# ebook_reader.net
KiCad netlist of a schematic drawn in EAGLE
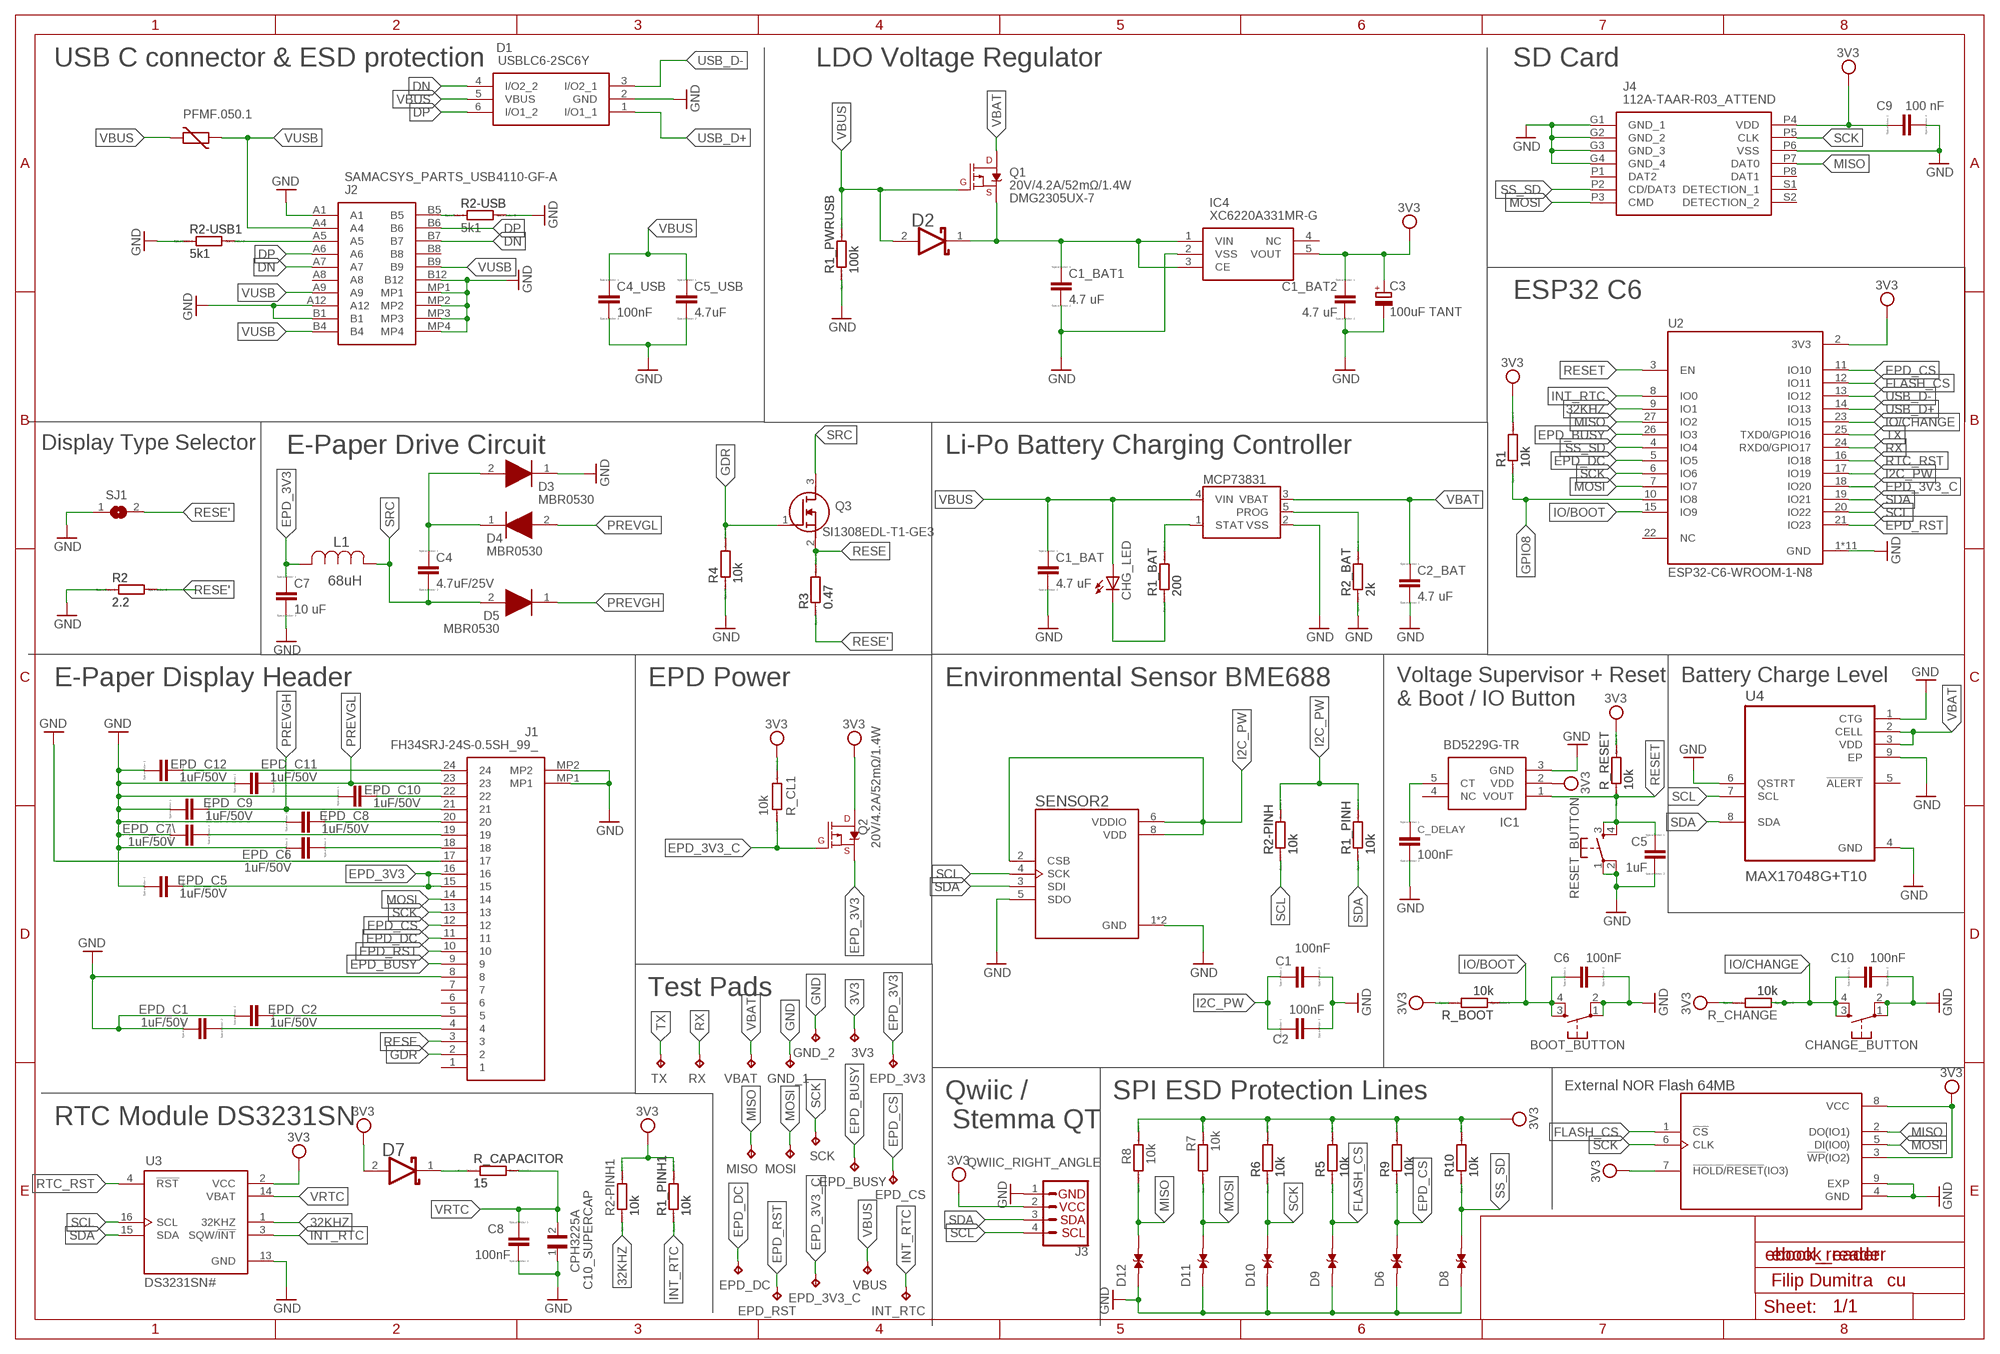
[diagram p0: schematic, sheet 1]

(export (version "E")
  (design (tool "Eeschema 10.0.6"))
  (components
    (comp (ref "3V3")
      (value "TPTP20R")
      (footprint "eagle-import:TP20R")
      (libsource (lib "eagle-import") (part "TPTP20R"))
    )
    (comp (ref "BOOT_BUTTON")
      (value "BUTTON_CUSYOMV1")
      (footprint "eagle-import:MYBUTTON")
      (libsource (lib "eagle-import") (part "BUTTON_CUSYOMV1"))
    )
    (comp (ref "C1")
      (value "100nF")
      (footprint "eagle-import:ESP32_WROVER_EAGLE-LTSPICE_C0402")
      (libsource (lib "eagle-import") (part "ESP32_WROVER_EAGLE-LTSPICE_CC0402"))
    )
    (comp (ref "C1_BAT")
      (value "4.7 uF")
      (footprint "eagle-import:ESP32_WROVER_EAGLE-LTSPICE_C0402")
      (libsource (lib "eagle-import") (part "ESP32_WROVER_EAGLE-LTSPICE_CC0402"))
    )
    (comp (ref "C1_BAT1")
      (value "4.7 uF")
      (footprint "eagle-import:ESP32_WROVER_EAGLE-LTSPICE_C0402")
      (libsource (lib "eagle-import") (part "ESP32_WROVER_EAGLE-LTSPICE_CC0402"))
    )
    (comp (ref "C1_BAT2")
      (value "4.7 uF")
      (footprint "eagle-import:ESP32_WROVER_EAGLE-LTSPICE_C0402")
      (libsource (lib "eagle-import") (part "ESP32_WROVER_EAGLE-LTSPICE_CC0402"))
    )
    (comp (ref "C2")
      (value "100nF")
      (footprint "eagle-import:ESP32_WROVER_EAGLE-LTSPICE_C0402")
      (libsource (lib "eagle-import") (part "ESP32_WROVER_EAGLE-LTSPICE_CC0402"))
    )
    (comp (ref "C2_BAT")
      (value "4.7 uF")
      (footprint "eagle-import:ESP32_WROVER_EAGLE-LTSPICE_C0402")
      (libsource (lib "eagle-import") (part "ESP32_WROVER_EAGLE-LTSPICE_CC0402"))
    )
    (comp (ref "C3")
      (value "100uF TANT")
      (footprint "eagle-import:RCL_CT3528")
      (libsource (lib "eagle-import") (part "RCL_CPOL-EUCT3528"))
    )
    (comp (ref "C4")
      (value "4.7uF/25V")
      (footprint "eagle-import:ESP32_WROVER_EAGLE-LTSPICE_C0402")
      (libsource (lib "eagle-import") (part "ESP32_WROVER_EAGLE-LTSPICE_CC0402"))
    )
    (comp (ref "C4_USB")
      (value "100nF")
      (footprint "eagle-import:ESP32_WROVER_EAGLE-LTSPICE_C0402")
      (libsource (lib "eagle-import") (part "ESP32_WROVER_EAGLE-LTSPICE_CC0402"))
    )
    (comp (ref "C5")
      (value "1uF")
      (footprint "eagle-import:ESP32_WROVER_EAGLE-LTSPICE_C0402")
      (libsource (lib "eagle-import") (part "ESP32_WROVER_EAGLE-LTSPICE_CC0402"))
    )
    (comp (ref "C5_USB")
      (value "4.7uF")
      (footprint "eagle-import:ESP32_WROVER_EAGLE-LTSPICE_C0402")
      (libsource (lib "eagle-import") (part "ESP32_WROVER_EAGLE-LTSPICE_CC0402"))
    )
    (comp (ref "C6")
      (value "100nF")
      (footprint "eagle-import:ESP32_WROVER_EAGLE-LTSPICE_C0402")
      (libsource (lib "eagle-import") (part "ESP32_WROVER_EAGLE-LTSPICE_CC0402"))
    )
    (comp (ref "C7")
      (value "10 uF")
      (footprint "eagle-import:ESP32_WROVER_EAGLE-LTSPICE_C0402")
      (libsource (lib "eagle-import") (part "ESP32_WROVER_EAGLE-LTSPICE_CC0402"))
    )
    (comp (ref "C8")
      (value "100nF")
      (footprint "eagle-import:ESP32_WROVER_EAGLE-LTSPICE_C0402")
      (libsource (lib "eagle-import") (part "ESP32_WROVER_EAGLE-LTSPICE_CC0402"))
    )
    (comp (ref "C9")
      (value "100 nF")
      (footprint "eagle-import:ESP32_WROVER_EAGLE-LTSPICE_C0402")
      (libsource (lib "eagle-import") (part "ESP32_WROVER_EAGLE-LTSPICE_CC0402"))
    )
    (comp (ref "C10")
      (value "100nF")
      (footprint "eagle-import:ESP32_WROVER_EAGLE-LTSPICE_C0402")
      (libsource (lib "eagle-import") (part "ESP32_WROVER_EAGLE-LTSPICE_CC0402"))
    )
    (comp (ref "C10_SUPERCAP")
      (value "CPH3225A")
      (footprint "eagle-import:CAPCP3225X100N")
      (fields (field (name "MF") "Seiko Instruments"))
      (libsource (lib "eagle-import") (part "CPH3225A"))
    )
    (comp (ref "CHANGE_BUTTON")
      (value "BUTTON_CUSYOMV1")
      (footprint "eagle-import:MYBUTTON")
      (libsource (lib "eagle-import") (part "BUTTON_CUSYOMV1"))
    )
    (comp (ref "CHG_LED")
      (value "ADAFRUIT_LEDCHIP-LED0603")
      (footprint "eagle-import:ADAFRUIT_CHIP-LED0603")
      (libsource (lib "eagle-import") (part "ADAFRUIT_LEDCHIP-LED0603"))
    )
    (comp (ref "C_DELAY")
      (value "100nF")
      (footprint "eagle-import:ESP32_WROVER_EAGLE-LTSPICE_C0402")
      (libsource (lib "eagle-import") (part "ESP32_WROVER_EAGLE-LTSPICE_CC0402"))
    )
    (comp (ref "D1")
      (value "USBLC6-2SC6Y")
      (footprint "eagle-import:SOT95P280X145-6N")
      (fields (field (name "MF") "STMicroelectronics"))
      (libsource (lib "eagle-import") (part "USBLC6-2SC6Y"))
    )
    (comp (ref "D2")
      (value "ESP32_WROVER_AVX---SD0805S020S1R0_AVX_SD0805S020S1R0_0_0AVX_SD0805S020S1R0_0_0")
      (footprint "eagle-import:ESP32_WROVER_AVX---SD0805S020S1R0_AVX_SD0805S020S1R0_0")
      (fields
        (field (name "DIGIKEY_PART_NUMBER") "478-7800-1-ND")
        (field (name "MF") "AVX")
        (field (name "MOUSER_PART_NUMBER") "581-SD0805S020S1R0")
      )
      (libsource (lib "eagle-import") (part "ESP32_WROVER_AVX---SD0805S020S1R0_AVX_SD0805S020S1R0_0_0AVX_SD0805S020S1R0_0_0"))
    )
    (comp (ref "D3")
      (value "MBR0530")
      (footprint "eagle-import:SOD3716X135N")
      (fields (field (name "MF") "ON Semiconductor"))
      (libsource (lib "eagle-import") (part "MBR0530"))
    )
    (comp (ref "D4")
      (value "MBR0530")
      (footprint "eagle-import:SOD3716X135N")
      (fields (field (name "MF") "ON Semiconductor"))
      (libsource (lib "eagle-import") (part "MBR0530"))
    )
    (comp (ref "D5")
      (value "MBR0530")
      (footprint "eagle-import:SOD3716X135N")
      (fields (field (name "MF") "ON Semiconductor"))
      (libsource (lib "eagle-import") (part "MBR0530"))
    )
    (comp (ref "D6")
      (value "PGB1010603MR")
      (footprint "eagle-import:DIOC1608X36N")
      (fields (field (name "MF") "Littelfuse Inc."))
      (libsource (lib "eagle-import") (part "PGB1010603MR"))
    )
    (comp (ref "D7")
      (value "ESP32_WROVER_AVX---SD0805S020S1R0_AVX_SD0805S020S1R0_0_0AVX_SD0805S020S1R0_0_0")
      (footprint "eagle-import:ESP32_WROVER_AVX---SD0805S020S1R0_AVX_SD0805S020S1R0_0")
      (fields
        (field (name "DIGIKEY_PART_NUMBER") "478-7800-1-ND")
        (field (name "MF") "AVX")
        (field (name "MOUSER_PART_NUMBER") "581-SD0805S020S1R0")
      )
      (libsource (lib "eagle-import") (part "ESP32_WROVER_AVX---SD0805S020S1R0_AVX_SD0805S020S1R0_0_0AVX_SD0805S020S1R0_0_0"))
    )
    (comp (ref "D8")
      (value "PGB1010603MR")
      (footprint "eagle-import:DIOC1608X36N")
      (fields (field (name "MF") "Littelfuse Inc."))
      (libsource (lib "eagle-import") (part "PGB1010603MR"))
    )
    (comp (ref "D9")
      (value "PGB1010603MR")
      (footprint "eagle-import:DIOC1608X36N")
      (fields (field (name "MF") "Littelfuse Inc."))
      (libsource (lib "eagle-import") (part "PGB1010603MR"))
    )
    (comp (ref "D10")
      (value "PGB1010603MR")
      (footprint "eagle-import:DIOC1608X36N")
      (fields (field (name "MF") "Littelfuse Inc."))
      (libsource (lib "eagle-import") (part "PGB1010603MR"))
    )
    (comp (ref "D11")
      (value "PGB1010603MR")
      (footprint "eagle-import:DIOC1608X36N")
      (fields (field (name "MF") "Littelfuse Inc."))
      (libsource (lib "eagle-import") (part "PGB1010603MR"))
    )
    (comp (ref "D12")
      (value "PGB1010603MR")
      (footprint "eagle-import:DIOC1608X36N")
      (fields (field (name "MF") "Littelfuse Inc."))
      (libsource (lib "eagle-import") (part "PGB1010603MR"))
    )
    (comp (ref "EPD_3V3")
      (value "TPTP20R")
      (footprint "eagle-import:TP20R")
      (libsource (lib "eagle-import") (part "TPTP20R"))
    )
    (comp (ref "EPD_3V3_C")
      (value "TPTP20R")
      (footprint "eagle-import:TP20R")
      (libsource (lib "eagle-import") (part "TPTP20R"))
    )
    (comp (ref "EPD_BUSY")
      (value "TPTP20R")
      (footprint "eagle-import:TP20R")
      (libsource (lib "eagle-import") (part "TPTP20R"))
    )
    (comp (ref "EPD_C1")
      (value "1uF/50V")
      (footprint "eagle-import:ESP32_WROVER_EAGLE-LTSPICE_C0402")
      (libsource (lib "eagle-import") (part "ESP32_WROVER_EAGLE-LTSPICE_CC0402"))
    )
    (comp (ref "EPD_C2")
      (value "1uF/50V")
      (footprint "eagle-import:ESP32_WROVER_EAGLE-LTSPICE_C0402")
      (libsource (lib "eagle-import") (part "ESP32_WROVER_EAGLE-LTSPICE_CC0402"))
    )
    (comp (ref "EPD_C5")
      (value "1uF/50V")
      (footprint "eagle-import:ESP32_WROVER_EAGLE-LTSPICE_C0402")
      (libsource (lib "eagle-import") (part "ESP32_WROVER_EAGLE-LTSPICE_CC0402"))
    )
    (comp (ref "EPD_C6")
      (value "1uF/50V")
      (footprint "eagle-import:ESP32_WROVER_EAGLE-LTSPICE_C0402")
      (libsource (lib "eagle-import") (part "ESP32_WROVER_EAGLE-LTSPICE_CC0402"))
    )
    (comp (ref "EPD_C7\\")
      (value "1uF/50V")
      (footprint "eagle-import:ESP32_WROVER_EAGLE-LTSPICE_C0402")
      (libsource (lib "eagle-import") (part "ESP32_WROVER_EAGLE-LTSPICE_CC0402"))
    )
    (comp (ref "EPD_C8")
      (value "1uF/50V")
      (footprint "eagle-import:ESP32_WROVER_EAGLE-LTSPICE_C0402")
      (libsource (lib "eagle-import") (part "ESP32_WROVER_EAGLE-LTSPICE_CC0402"))
    )
    (comp (ref "EPD_C9")
      (value "1uF/50V")
      (footprint "eagle-import:ESP32_WROVER_EAGLE-LTSPICE_C0402")
      (libsource (lib "eagle-import") (part "ESP32_WROVER_EAGLE-LTSPICE_CC0402"))
    )
    (comp (ref "EPD_C10")
      (value "1uF/50V")
      (footprint "eagle-import:ESP32_WROVER_EAGLE-LTSPICE_C0402")
      (libsource (lib "eagle-import") (part "ESP32_WROVER_EAGLE-LTSPICE_CC0402"))
    )
    (comp (ref "EPD_C11")
      (value "1uF/50V")
      (footprint "eagle-import:ESP32_WROVER_EAGLE-LTSPICE_C0402")
      (libsource (lib "eagle-import") (part "ESP32_WROVER_EAGLE-LTSPICE_CC0402"))
    )
    (comp (ref "EPD_C12")
      (value "1uF/50V")
      (footprint "eagle-import:ESP32_WROVER_EAGLE-LTSPICE_C0402")
      (libsource (lib "eagle-import") (part "ESP32_WROVER_EAGLE-LTSPICE_CC0402"))
    )
    (comp (ref "EPD_CS")
      (value "TPTP20R")
      (footprint "eagle-import:TP20R")
      (libsource (lib "eagle-import") (part "TPTP20R"))
    )
    (comp (ref "EPD_DC")
      (value "TPTP20R")
      (footprint "eagle-import:TP20R")
      (libsource (lib "eagle-import") (part "TPTP20R"))
    )
    (comp (ref "EPD_RST")
      (value "TPTP20R")
      (footprint "eagle-import:TP20R")
      (libsource (lib "eagle-import") (part "TPTP20R"))
    )
    (comp (ref "GND_1")
      (value "TPTP20R")
      (footprint "eagle-import:TP20R")
      (libsource (lib "eagle-import") (part "TPTP20R"))
    )
    (comp (ref "GND_2")
      (value "TPTP20R")
      (footprint "eagle-import:TP20R")
      (libsource (lib "eagle-import") (part "TPTP20R"))
    )
    (comp (ref "IC1")
      (value "BD5229G-TR")
      (footprint "eagle-import:SOT95P280X125-5N")
      (fields (field (name "MOUSER_PART_NUMBER") "755-BD5229G-TR"))
      (libsource (lib "eagle-import") (part "BD5229G-TR"))
    )
    (comp (ref "IC4")
      (value "XC6220A331MR-G")
      (footprint "eagle-import:SOT95P280X120-5N")
      (fields (field (name "MOUSER_PART_NUMBER") "865-XC6220A331MR-G"))
      (libsource (lib "eagle-import") (part "XC6220A331MR-G"))
    )
    (comp (ref "INT_RTC")
      (value "TPTP20R")
      (footprint "eagle-import:TP20R")
      (libsource (lib "eagle-import") (part "TPTP20R"))
    )
    (comp (ref "J1")
      (value "FH34SRJ-24S-0.5SH_99_")
      (footprint "eagle-import:FH34SRJ24S05SH99")
      (fields
        (field (name "MANUFACTURER_PART_NUMBER") "FH34SRJ-24S-0.5SH(99)")
        (field (name "MOUSER_PART_NUMBER") "798-FH34SRJ24S05SH99")
      )
      (libsource (lib "eagle-import") (part "FH34SRJ-24S-0.5SH_99_"))
    )
    (comp (ref "J2")
      (value "SAMACSYS_PARTS_USB4110-GF-A")
      (footprint "eagle-import:SAMACSYS_PARTS_USB4110GFA")
      (fields
        (field (name "MANUFACTURER_PART_NUMBER") "USB4110-GF-A")
        (field (name "MOUSER_PART_NUMBER") "640-USB4110-GF-A")
      )
      (libsource (lib "eagle-import") (part "SAMACSYS_PARTS_USB4110-GF-A"))
    )
    (comp (ref "J3")
      (value "QWIIC_RIGHT_ANGLE")
      (footprint "eagle-import:JST04_1MM_RA")
      (libsource (lib "eagle-import") (part "QWIIC_CONNECTORJS-1MM"))
    )
    (comp (ref "J4")
      (value "112A-TAAR-R03_ATTEND")
      (footprint "eagle-import:112ATAARR03ATTEND")
      (fields (field (name "MANUFACTURER_PART_NUMBER") "112A-TAAR-R03 ATTEND"))
      (libsource (lib "eagle-import") (part "112A-TAAR-R03_ATTEND"))
    )
    (comp (ref "L1")
      (value "68uH")
      (footprint "eagle-import:IND_4828-WE-TPC_WRE")
      (fields
        (field (name "MANUFACTURER_PART_NUMBER") "744043680")
        (field (name "COPYRIGHT") "Copyright (C) 2024 Ultra Librarian. All rights reserved.")
      )
      (libsource (lib "eagle-import") (part "744043680IND_4828-WE-TPC_WRE"))
    )
    (comp (ref "MCP73831")
      (value "ESP32_WROVER_SPARKFUN-IC-POWER_MCP73831")
      (footprint "eagle-import:ESP32_WROVER_SPARKFUN-IC-POWER_SOT23-5")
      (libsource (lib "eagle-import") (part "ESP32_WROVER_SPARKFUN-IC-POWER_MCP73831"))
    )
    (comp (ref "MISO")
      (value "TPTP20R")
      (footprint "eagle-import:TP20R")
      (libsource (lib "eagle-import") (part "TPTP20R"))
    )
    (comp (ref "MOSI")
      (value "TPTP20R")
      (footprint "eagle-import:TP20R")
      (libsource (lib "eagle-import") (part "TPTP20R"))
    )
    (comp (ref "PFMF.050.1")
      (value "ESP32C6_VARISTORCN1812")
      (footprint "eagle-import:ESP32C6_VARISTOR_CT_CN1812")
      (libsource (lib "eagle-import") (part "ESP32C6_VARISTORCN1812"))
    )
    (comp (ref "Q1")
      (value "20V/4.2A/52mΩ/1.4W")
      (footprint "eagle-import:ESP32_WROVER_SPARKFUN-DISCRETESEMI_SOT23-3")
      (libsource (lib "eagle-import") (part "ESP32_WROVER_SPARKFUN-DISCRETESEMI_MOSFET_PCH-DMG2305UX-7"))
    )
    (comp (ref "Q2")
      (value "20V/4.2A/52mΩ/1.4W")
      (footprint "eagle-import:ESP32_WROVER_SPARKFUN-DISCRETESEMI_SOT23-3")
      (libsource (lib "eagle-import") (part "ESP32_WROVER_SPARKFUN-DISCRETESEMI_MOSFET_PCH-DMG2305UX-7"))
    )
    (comp (ref "Q3")
      (value "SI1308EDL-T1-GE3")
      (footprint "eagle-import:SOT65P210X110-3N")
      (fields (field (name "MF") "Vishay Siliconix"))
      (libsource (lib "eagle-import") (part "SI1308EDL-T1-GE3"))
    )
    (comp (ref "R1")
      (value "10k")
      (footprint "eagle-import:ESP32_WROVER_EAGLE-LTSPICE_R0402")
      (libsource (lib "eagle-import") (part "ESP32_WROVER_EAGLE-LTSPICE_RR0402"))
    )
    (comp (ref "R1_BAT")
      (value "200")
      (footprint "eagle-import:ESP32_WROVER_EAGLE-LTSPICE_R0402")
      (libsource (lib "eagle-import") (part "ESP32_WROVER_EAGLE-LTSPICE_RR0402"))
    )
    (comp (ref "R1_PINH")
      (value "10k")
      (footprint "eagle-import:ESP32_WROVER_EAGLE-LTSPICE_R0402")
      (libsource (lib "eagle-import") (part "ESP32_WROVER_EAGLE-LTSPICE_RR0402"))
    )
    (comp (ref "R1_PINH1")
      (value "10k")
      (footprint "eagle-import:ESP32_WROVER_EAGLE-LTSPICE_R0402")
      (libsource (lib "eagle-import") (part "ESP32_WROVER_EAGLE-LTSPICE_RR0402"))
    )
    (comp (ref "R1_PWRUSB")
      (value "100k")
      (footprint "eagle-import:ESP32_WROVER_EAGLE-LTSPICE_R0402")
      (libsource (lib "eagle-import") (part "ESP32_WROVER_EAGLE-LTSPICE_RR0402"))
    )
    (comp (ref "R2")
      (value "2.2")
      (footprint "eagle-import:ESP32_WROVER_EAGLE-LTSPICE_R0402")
      (libsource (lib "eagle-import") (part "ESP32_WROVER_EAGLE-LTSPICE_RR0402"))
    )
    (comp (ref "R2-PINH")
      (value "10k")
      (footprint "eagle-import:ESP32_WROVER_EAGLE-LTSPICE_R0402")
      (libsource (lib "eagle-import") (part "ESP32_WROVER_EAGLE-LTSPICE_RR0402"))
    )
    (comp (ref "R2-PINH1")
      (value "10k")
      (footprint "eagle-import:ESP32_WROVER_EAGLE-LTSPICE_R0402")
      (libsource (lib "eagle-import") (part "ESP32_WROVER_EAGLE-LTSPICE_RR0402"))
    )
    (comp (ref "R2-USB")
      (value "5k1")
      (footprint "eagle-import:ESP32_WROVER_EAGLE-LTSPICE_R0402")
      (libsource (lib "eagle-import") (part "ESP32_WROVER_EAGLE-LTSPICE_RR0402"))
    )
    (comp (ref "R2-USB1")
      (value "5k1")
      (footprint "eagle-import:ESP32_WROVER_EAGLE-LTSPICE_R0402")
      (libsource (lib "eagle-import") (part "ESP32_WROVER_EAGLE-LTSPICE_RR0402"))
    )
    (comp (ref "R2_BAT")
      (value "2k")
      (footprint "eagle-import:ESP32_WROVER_EAGLE-LTSPICE_R0402")
      (libsource (lib "eagle-import") (part "ESP32_WROVER_EAGLE-LTSPICE_RR0402"))
    )
    (comp (ref "R3")
      (value "0.47")
      (footprint "eagle-import:ESP32_WROVER_EAGLE-LTSPICE_R0402")
      (libsource (lib "eagle-import") (part "ESP32_WROVER_EAGLE-LTSPICE_RR0402"))
    )
    (comp (ref "R4")
      (value "10k")
      (footprint "eagle-import:ESP32_WROVER_EAGLE-LTSPICE_R0402")
      (libsource (lib "eagle-import") (part "ESP32_WROVER_EAGLE-LTSPICE_RR0402"))
    )
    (comp (ref "R5")
      (value "10k")
      (footprint "eagle-import:ESP32_WROVER_EAGLE-LTSPICE_R0402")
      (libsource (lib "eagle-import") (part "ESP32_WROVER_EAGLE-LTSPICE_RR0402"))
    )
    (comp (ref "R6")
      (value "10k")
      (footprint "eagle-import:ESP32_WROVER_EAGLE-LTSPICE_R0402")
      (libsource (lib "eagle-import") (part "ESP32_WROVER_EAGLE-LTSPICE_RR0402"))
    )
    (comp (ref "R7")
      (value "10k")
      (footprint "eagle-import:ESP32_WROVER_EAGLE-LTSPICE_R0402")
      (libsource (lib "eagle-import") (part "ESP32_WROVER_EAGLE-LTSPICE_RR0402"))
    )
    (comp (ref "R8")
      (value "10k")
      (footprint "eagle-import:ESP32_WROVER_EAGLE-LTSPICE_R0402")
      (libsource (lib "eagle-import") (part "ESP32_WROVER_EAGLE-LTSPICE_RR0402"))
    )
    (comp (ref "R9")
      (value "10k")
      (footprint "eagle-import:ESP32_WROVER_EAGLE-LTSPICE_R0402")
      (libsource (lib "eagle-import") (part "ESP32_WROVER_EAGLE-LTSPICE_RR0402"))
    )
    (comp (ref "R10")
      (value "10k")
      (footprint "eagle-import:ESP32_WROVER_EAGLE-LTSPICE_R0402")
      (libsource (lib "eagle-import") (part "ESP32_WROVER_EAGLE-LTSPICE_RR0402"))
    )
    (comp (ref "RESET_BUTTON")
      (value "BUTTON_CUSYOMV1")
      (footprint "eagle-import:MYBUTTON")
      (libsource (lib "eagle-import") (part "BUTTON_CUSYOMV1"))
    )
    (comp (ref "RX")
      (value "TPTP20R")
      (footprint "eagle-import:TP20R")
      (libsource (lib "eagle-import") (part "TPTP20R"))
    )
    (comp (ref "R_BOOT")
      (value "10k")
      (footprint "eagle-import:ESP32_WROVER_EAGLE-LTSPICE_R0402")
      (libsource (lib "eagle-import") (part "ESP32_WROVER_EAGLE-LTSPICE_RR0402"))
    )
    (comp (ref "R_CAPACITOR")
      (value "15")
      (footprint "eagle-import:ESP32_WROVER_EAGLE-LTSPICE_R0402")
      (libsource (lib "eagle-import") (part "ESP32_WROVER_EAGLE-LTSPICE_RR0402"))
    )
    (comp (ref "R_CHANGE")
      (value "10k")
      (footprint "eagle-import:ESP32_WROVER_EAGLE-LTSPICE_R0402")
      (libsource (lib "eagle-import") (part "ESP32_WROVER_EAGLE-LTSPICE_RR0402"))
    )
    (comp (ref "R_CL1")
      (value "10k")
      (footprint "eagle-import:ESP32_WROVER_EAGLE-LTSPICE_R0402")
      (libsource (lib "eagle-import") (part "ESP32_WROVER_EAGLE-LTSPICE_RR0402"))
    )
    (comp (ref "R_RESET")
      (value "10k")
      (footprint "eagle-import:ESP32_WROVER_EAGLE-LTSPICE_R0402")
      (libsource (lib "eagle-import") (part "ESP32_WROVER_EAGLE-LTSPICE_RR0402"))
    )
    (comp (ref "SCK")
      (value "TPTP20R")
      (footprint "eagle-import:TP20R")
      (libsource (lib "eagle-import") (part "TPTP20R"))
    )
    (comp (ref "SENSOR2")
      (value "ESP32_WROVER_BME680_BME680")
      (footprint "eagle-import:ESP32_WROVER_BME680_PSON80P300X300X100-8N")
      (fields (field (name "MF") "Bosch Sensortec") (field (name "MP") "BME680"))
      (libsource (lib "eagle-import") (part "ESP32_WROVER_BME680_BME680"))
    )
    (comp (ref "SJ1") (value "SJ") (footprint "eagle-import:SJ") (libsource (lib "eagle-import") (part "SJ")))
    (comp (ref "TX")
      (value "TPTP20R")
      (footprint "eagle-import:TP20R")
      (libsource (lib "eagle-import") (part "TPTP20R"))
    )
    (comp (ref "U1")
      (value "W25Q512JVEIQ")
      (footprint "eagle-import:SON127P600X800X80-9N")
      (fields (field (name "MF") "Winbond Electronics"))
      (libsource (lib "eagle-import") (part "W25Q512JVEIQ"))
    )
    (comp (ref "U2")
      (value "ESP32-C6-WROOM-1-N8")
      (footprint "eagle-import:XCVR_ESP32-C6-WROOM-1-N8")
      (fields (field (name "MF") "Espressif Systems"))
      (libsource (lib "eagle-import") (part "ESP32-C6-WROOM-1-N8"))
    )
    (comp (ref "U3")
      (value "DS3231SN#")
      (footprint "eagle-import:SOIC127P1032X265-16N")
      (fields (field (name "MF") "Analog Devices"))
      (libsource (lib "eagle-import") (part "DS3231SN#"))
    )
    (comp (ref "U4")
      (value "MAX17048G+T10")
      (footprint "eagle-import:SON50P200X200X80-9N")
      (fields (field (name "MF") "Analog Devices"))
      (libsource (lib "eagle-import") (part "MAX17048G+T10"))
    )
    (comp (ref "VBAT")
      (value "TPTP20R")
      (footprint "eagle-import:TP20R")
      (libsource (lib "eagle-import") (part "TPTP20R"))
    )
    (comp (ref "VBUS")
      (value "TPTP20R")
      (footprint "eagle-import:TP20R")
      (libsource (lib "eagle-import") (part "TPTP20R"))
    )
  )
  (nets
    (net (code "1") (name "3V3") (class "Default")
      (node (ref "3V3") (pin "TP") (pinfunction "TP_TP") (pintype "input"))
      (node (ref "C1_BAT2") (pin "1") (pinfunction "1_1") (pintype "passive"))
      (node (ref "C3") (pin "+") (pinfunction "+_+") (pintype "passive"))
      (node (ref "C9") (pin "1") (pinfunction "1_1") (pintype "passive"))
      (node (ref "D7") (pin "2") (pinfunction "ANODE_2") (pintype "bidirectional"))
      (node (ref "IC1") (pin "2") (pinfunction "VDD_2") (pintype "bidirectional"))
      (node (ref "IC4") (pin "5") (pinfunction "VOUT_5") (pintype "bidirectional"))
      (node (ref "J3") (pin "2") (pinfunction "2_2") (pintype "power_in"))
      (node (ref "J4") (pin "P4") (pinfunction "VDD_P4") (pintype "bidirectional"))
      (node (ref "Q2") (pin "3") (pinfunction "D_3") (pintype "bidirectional"))
      (node (ref "R1") (pin "2") (pinfunction "2_2") (pintype "passive"))
      (node (ref "R10") (pin "2") (pinfunction "2_2") (pintype "passive"))
      (node (ref "R1_PINH1") (pin "2") (pinfunction "2_2") (pintype "passive"))
      (node (ref "R2-PINH1") (pin "2") (pinfunction "2_2") (pintype "passive"))
      (node (ref "R5") (pin "2") (pinfunction "2_2") (pintype "passive"))
      (node (ref "R6") (pin "2") (pinfunction "2_2") (pintype "passive"))
      (node (ref "R7") (pin "2") (pinfunction "2_2") (pintype "passive"))
      (node (ref "R8") (pin "2") (pinfunction "2_2") (pintype "passive"))
      (node (ref "R9") (pin "2") (pinfunction "2_2") (pintype "passive"))
      (node (ref "R_BOOT") (pin "2") (pinfunction "2_2") (pintype "passive"))
      (node (ref "R_CHANGE") (pin "2") (pinfunction "2_2") (pintype "passive"))
      (node (ref "R_CL1") (pin "2") (pinfunction "2_2") (pintype "passive"))
      (node (ref "R_RESET") (pin "2") (pinfunction "2_2") (pintype "passive"))
      (node (ref "U1") (pin "3") (pinfunction "~{WP}(IO2)_3") (pintype "bidirectional"))
      (node (ref "U1") (pin "7") (pinfunction "~{HOLD}/~{RESET}(IO3)_7") (pintype "bidirectional"))
      (node (ref "U1") (pin "8") (pinfunction "VCC_8") (pintype "power_in"))
      (node (ref "U2") (pin "2") (pinfunction "3V3_2") (pintype "power_in"))
      (node (ref "U3") (pin "2") (pinfunction "VCC_2") (pintype "power_in"))
    )
    (net (code "2") (name "32KHZ") (class "Default")
      (node (ref "R2-PINH1") (pin "1") (pinfunction "1_1") (pintype "passive"))
      (node (ref "U2") (pin "9") (pinfunction "IO1_9") (pintype "bidirectional"))
      (node (ref "U3") (pin "1") (pinfunction "32KHZ_1") (pintype "output"))
    )
    (net (code "3") (name "DN") (class "Default")
      (node (ref "D1") (pin "4") (pinfunction "I/O2_2_4") (pintype "bidirectional"))
      (node (ref "J2") (pin "A7") (pinfunction "A7_A7") (pintype "bidirectional"))
      (node (ref "J2") (pin "B7") (pinfunction "B7_B7") (pintype "bidirectional"))
    )
    (net (code "4") (name "DP") (class "Default")
      (node (ref "D1") (pin "6") (pinfunction "I/O1_2_6") (pintype "bidirectional"))
      (node (ref "J2") (pin "A6") (pinfunction "A6_A6") (pintype "bidirectional"))
      (node (ref "J2") (pin "B6") (pinfunction "B6_B6") (pintype "bidirectional"))
    )
    (net (code "5") (name "EPD_3V3") (class "Default")
      (node (ref "C7") (pin "1") (pinfunction "1_1") (pintype "passive"))
      (node (ref "EPD_3V3") (pin "TP") (pinfunction "TP_TP") (pintype "input"))
      (node (ref "EPD_C5") (pin "2") (pinfunction "2_2") (pintype "passive"))
      (node (ref "J1") (pin "15") (pinfunction "15_15") (pintype "bidirectional"))
      (node (ref "J1") (pin "16") (pinfunction "16_16") (pintype "bidirectional"))
      (node (ref "L1") (pin "2") (pinfunction "2_2") (pintype "passive"))
      (node (ref "Q2") (pin "2") (pinfunction "S_2") (pintype "bidirectional"))
    )
    (net (code "6") (name "EPD_3V3_C") (class "Default")
      (node (ref "EPD_3V3_C") (pin "TP") (pinfunction "TP_TP") (pintype "input"))
      (node (ref "Q2") (pin "1") (pinfunction "G_1") (pintype "bidirectional"))
      (node (ref "R_CL1") (pin "1") (pinfunction "1_1") (pintype "passive"))
      (node (ref "U2") (pin "18") (pinfunction "IO20_18") (pintype "bidirectional"))
    )
    (net (code "7") (name "EPD_BUSY") (class "Default")
      (node (ref "EPD_BUSY") (pin "TP") (pinfunction "TP_TP") (pintype "input"))
      (node (ref "J1") (pin "9") (pinfunction "9_9") (pintype "bidirectional"))
      (node (ref "U2") (pin "26") (pinfunction "IO3_26") (pintype "bidirectional"))
    )
    (net (code "8") (name "EPD_CS") (class "Default")
      (node (ref "D6") (pin "2") (pinfunction "2_2") (pintype "passive"))
      (node (ref "EPD_CS") (pin "TP") (pinfunction "TP_TP") (pintype "input"))
      (node (ref "J1") (pin "12") (pinfunction "12_12") (pintype "bidirectional"))
      (node (ref "R9") (pin "1") (pinfunction "1_1") (pintype "passive"))
      (node (ref "U2") (pin "11") (pinfunction "IO10_11") (pintype "bidirectional"))
    )
    (net (code "9") (name "EPD_DC") (class "Default")
      (node (ref "EPD_DC") (pin "TP") (pinfunction "TP_TP") (pintype "input"))
      (node (ref "J1") (pin "11") (pinfunction "11_11") (pintype "bidirectional"))
      (node (ref "U2") (pin "5") (pinfunction "IO5_5") (pintype "bidirectional"))
    )
    (net (code "10") (name "EPD_RST") (class "Default")
      (node (ref "EPD_RST") (pin "TP") (pinfunction "TP_TP") (pintype "input"))
      (node (ref "J1") (pin "10") (pinfunction "10_10") (pintype "bidirectional"))
      (node (ref "U2") (pin "21") (pinfunction "IO23_21") (pintype "bidirectional"))
    )
    (net (code "11") (name "FLASH_CS") (class "Default")
      (node (ref "D9") (pin "2") (pinfunction "2_2") (pintype "passive"))
      (node (ref "R5") (pin "1") (pinfunction "1_1") (pintype "passive"))
      (node (ref "U1") (pin "1") (pinfunction "~{CS}_1") (pintype "input"))
      (node (ref "U2") (pin "12") (pinfunction "IO11_12") (pintype "bidirectional"))
    )
    (net (code "12") (name "GDR") (class "Default")
      (node (ref "J1") (pin "2") (pinfunction "2_2") (pintype "bidirectional"))
      (node (ref "Q3") (pin "1") (pinfunction "G_1") (pintype "bidirectional"))
      (node (ref "R4") (pin "2") (pinfunction "2_2") (pintype "passive"))
    )
    (net (code "13") (name "GND") (class "Default")
      (node (ref "BOOT_BUTTON") (pin "1") (pinfunction "1_1") (pintype "passive"))
      (node (ref "BOOT_BUTTON") (pin "2") (pinfunction "2_2") (pintype "passive"))
      (node (ref "C1") (pin "2") (pinfunction "2_2") (pintype "passive"))
      (node (ref "C10") (pin "2") (pinfunction "2_2") (pintype "passive"))
      (node (ref "C10_SUPERCAP") (pin "1") (pinfunction "1_1") (pintype "passive"))
      (node (ref "C1_BAT") (pin "2") (pinfunction "2_2") (pintype "passive"))
      (node (ref "C1_BAT1") (pin "2") (pinfunction "2_2") (pintype "passive"))
      (node (ref "C1_BAT2") (pin "2") (pinfunction "2_2") (pintype "passive"))
      (node (ref "C2") (pin "2") (pinfunction "2_2") (pintype "passive"))
      (node (ref "C2_BAT") (pin "2") (pinfunction "2_2") (pintype "passive"))
      (node (ref "C3") (pin "-") (pinfunction "-_-") (pintype "passive"))
      (node (ref "C4_USB") (pin "2") (pinfunction "2_2") (pintype "passive"))
      (node (ref "C5") (pin "2") (pinfunction "2_2") (pintype "passive"))
      (node (ref "C5_USB") (pin "2") (pinfunction "2_2") (pintype "passive"))
      (node (ref "C6") (pin "2") (pinfunction "2_2") (pintype "passive"))
      (node (ref "C7") (pin "2") (pinfunction "2_2") (pintype "passive"))
      (node (ref "C8") (pin "2") (pinfunction "2_2") (pintype "passive"))
      (node (ref "C9") (pin "2") (pinfunction "2_2") (pintype "passive"))
      (node (ref "CHANGE_BUTTON") (pin "1") (pinfunction "1_1") (pintype "passive"))
      (node (ref "CHANGE_BUTTON") (pin "2") (pinfunction "2_2") (pintype "passive"))
      (node (ref "C_DELAY") (pin "2") (pinfunction "2_2") (pintype "passive"))
      (node (ref "D1") (pin "2") (pinfunction "GND_2") (pintype "bidirectional"))
      (node (ref "D10") (pin "1") (pinfunction "1_1") (pintype "passive"))
      (node (ref "D11") (pin "1") (pinfunction "1_1") (pintype "passive"))
      (node (ref "D12") (pin "1") (pinfunction "1_1") (pintype "passive"))
      (node (ref "D3") (pin "1") (pinfunction "K_1") (pintype "bidirectional"))
      (node (ref "D6") (pin "1") (pinfunction "1_1") (pintype "passive"))
      (node (ref "D8") (pin "1") (pinfunction "1_1") (pintype "passive"))
      (node (ref "D9") (pin "1") (pinfunction "1_1") (pintype "passive"))
      (node (ref "EPD_C1") (pin "1") (pinfunction "1_1") (pintype "passive"))
      (node (ref "EPD_C10") (pin "1") (pinfunction "1_1") (pintype "passive"))
      (node (ref "EPD_C11") (pin "1") (pinfunction "1_1") (pintype "passive"))
      (node (ref "EPD_C12") (pin "1") (pinfunction "1_1") (pintype "passive"))
      (node (ref "EPD_C2") (pin "1") (pinfunction "1_1") (pintype "passive"))
      (node (ref "EPD_C5") (pin "1") (pinfunction "1_1") (pintype "passive"))
      (node (ref "EPD_C6") (pin "1") (pinfunction "1_1") (pintype "passive"))
      (node (ref "EPD_C7\\") (pin "1") (pinfunction "1_1") (pintype "passive"))
      (node (ref "EPD_C8") (pin "1") (pinfunction "1_1") (pintype "passive"))
      (node (ref "EPD_C9") (pin "1") (pinfunction "1_1") (pintype "passive"))
      (node (ref "GND_1") (pin "TP") (pinfunction "TP_TP") (pintype "input"))
      (node (ref "GND_2") (pin "TP") (pinfunction "TP_TP") (pintype "input"))
      (node (ref "IC1") (pin "3") (pinfunction "GND_3") (pintype "bidirectional"))
      (node (ref "IC4") (pin "2") (pinfunction "VSS_2") (pintype "bidirectional"))
      (node (ref "J1") (pin "17") (pinfunction "17_17") (pintype "bidirectional"))
      (node (ref "J1") (pin "8") (pinfunction "8_8") (pintype "bidirectional"))
      (node (ref "J1") (pin "MP1") (pinfunction "MP1_MP1") (pintype "bidirectional"))
      (node (ref "J1") (pin "MP2") (pinfunction "MP2_MP2") (pintype "bidirectional"))
      (node (ref "J2") (pin "A1") (pinfunction "A1_A1") (pintype "bidirectional"))
      (node (ref "J2") (pin "A12") (pinfunction "A12_A12") (pintype "bidirectional"))
      (node (ref "J2") (pin "B1") (pinfunction "B1_B1") (pintype "bidirectional"))
      (node (ref "J2") (pin "B12") (pinfunction "B12_B12") (pintype "bidirectional"))
      (node (ref "J2") (pin "MP1") (pinfunction "MP1_MP1") (pintype "bidirectional"))
      (node (ref "J2") (pin "MP2") (pinfunction "MP2_MP2") (pintype "bidirectional"))
      (node (ref "J2") (pin "MP3") (pinfunction "MP3_MP3") (pintype "bidirectional"))
      (node (ref "J2") (pin "MP4") (pinfunction "MP4_MP4") (pintype "bidirectional"))
      (node (ref "J3") (pin "1") (pinfunction "1_1") (pintype "power_in"))
      (node (ref "J4") (pin "G1") (pinfunction "GND_1_G1") (pintype "bidirectional"))
      (node (ref "J4") (pin "G2") (pinfunction "GND_2_G2") (pintype "bidirectional"))
      (node (ref "J4") (pin "G3") (pinfunction "GND_3_G3") (pintype "bidirectional"))
      (node (ref "J4") (pin "G4") (pinfunction "GND_4_G4") (pintype "bidirectional"))
      (node (ref "J4") (pin "P6") (pinfunction "VSS_P6") (pintype "bidirectional"))
      (node (ref "MCP73831") (pin "2") (pinfunction "VSS_2") (pintype "power_in"))
      (node (ref "R1_PWRUSB") (pin "1") (pinfunction "1_1") (pintype "passive"))
      (node (ref "R2") (pin "1") (pinfunction "1_1") (pintype "passive"))
      (node (ref "R2-USB") (pin "2") (pinfunction "2_2") (pintype "passive"))
      (node (ref "R2-USB1") (pin "1") (pinfunction "1_1") (pintype "passive"))
      (node (ref "R2_BAT") (pin "1") (pinfunction "1_1") (pintype "passive"))
      (node (ref "R4") (pin "1") (pinfunction "1_1") (pintype "passive"))
      (node (ref "RESET_BUTTON") (pin "1") (pinfunction "1_1") (pintype "passive"))
      (node (ref "RESET_BUTTON") (pin "2") (pinfunction "2_2") (pintype "passive"))
      (node (ref "SENSOR2") (pin "1") (pinfunction "GND_1") (pintype "power_in"))
      (node (ref "SENSOR2") (pin "5") (pinfunction "SDO_5") (pintype "bidirectional"))
      (node (ref "SENSOR2") (pin "7") (pinfunction "GND_7") (pintype "power_in"))
      (node (ref "SJ1") (pin "1") (pinfunction "1_1") (pintype "passive"))
      (node (ref "U1") (pin "4") (pinfunction "GND_4") (pintype "power_in"))
      (node (ref "U1") (pin "9") (pinfunction "EXP_9") (pintype "passive"))
      (node (ref "U2") (pin "1") (pinfunction "GND_1") (pintype "power_in"))
      (node (ref "U2") (pin "28") (pinfunction "GND_28") (pintype "power_in"))
      (node (ref "U2") (pin "29_1") (pinfunction "GND_29_1") (pintype "power_in"))
      (node (ref "U2") (pin "29_2") (pinfunction "GND_29_2") (pintype "power_in"))
      (node (ref "U2") (pin "29_3") (pinfunction "GND_29_3") (pintype "power_in"))
      (node (ref "U2") (pin "29_4") (pinfunction "GND_29_4") (pintype "power_in"))
      (node (ref "U2") (pin "29_5") (pinfunction "GND_29_5") (pintype "power_in"))
      (node (ref "U2") (pin "29_6") (pinfunction "GND_29_6") (pintype "power_in"))
      (node (ref "U2") (pin "29_7") (pinfunction "GND_29_7") (pintype "power_in"))
      (node (ref "U2") (pin "29_8") (pinfunction "GND_29_8") (pintype "power_in"))
      (node (ref "U2") (pin "29_9") (pinfunction "GND_29_9") (pintype "power_in"))
      (node (ref "U3") (pin "13") (pinfunction "GND_13") (pintype "power_in"))
      (node (ref "U4") (pin "1") (pinfunction "CTG_1") (pintype "power_in"))
      (node (ref "U4") (pin "4") (pinfunction "GND_4") (pintype "power_in"))
      (node (ref "U4") (pin "6") (pinfunction "QSTRT_6") (pintype "input"))
      (node (ref "U4") (pin "9") (pinfunction "EP_9") (pintype "power_in"))
    )
    (net (code "14") (name "GPIO8") (class "Default")
      (node (ref "R1") (pin "1") (pinfunction "1_1") (pintype "passive"))
      (node (ref "U2") (pin "10") (pinfunction "IO8_10") (pintype "bidirectional"))
    )
    (net (code "15") (name "I2C_PW") (class "Default")
      (node (ref "C1") (pin "1") (pinfunction "1_1") (pintype "passive"))
      (node (ref "C2") (pin "1") (pinfunction "1_1") (pintype "passive"))
      (node (ref "R1_PINH") (pin "2") (pinfunction "2_2") (pintype "passive"))
      (node (ref "R2-PINH") (pin "2") (pinfunction "2_2") (pintype "passive"))
      (node (ref "SENSOR2") (pin "2") (pinfunction "CSB_2") (pintype "input"))
      (node (ref "SENSOR2") (pin "6") (pinfunction "VDDIO_6") (pintype "power_in"))
      (node (ref "SENSOR2") (pin "8") (pinfunction "VDD_8") (pintype "power_in"))
      (node (ref "U2") (pin "17") (pinfunction "IO19_17") (pintype "bidirectional"))
    )
    (net (code "16") (name "INT_RTC") (class "Default")
      (node (ref "INT_RTC") (pin "TP") (pinfunction "TP_TP") (pintype "input"))
      (node (ref "R1_PINH1") (pin "1") (pinfunction "1_1") (pintype "passive"))
      (node (ref "U2") (pin "8") (pinfunction "IO0_8") (pintype "bidirectional"))
      (node (ref "U3") (pin "3") (pinfunction "SQW/~{INT}_3") (pintype "output"))
    )
    (net (code "17") (name "IO{slash}BOOT") (class "Default")
      (node (ref "BOOT_BUTTON") (pin "3") (pinfunction "3_3") (pintype "passive"))
      (node (ref "BOOT_BUTTON") (pin "4") (pinfunction "4_4") (pintype "passive"))
      (node (ref "C6") (pin "1") (pinfunction "1_1") (pintype "passive"))
      (node (ref "R_BOOT") (pin "1") (pinfunction "1_1") (pintype "passive"))
      (node (ref "U2") (pin "15") (pinfunction "IO9_15") (pintype "bidirectional"))
    )
    (net (code "18") (name "IO{slash}CHANGE") (class "Default")
      (node (ref "C10") (pin "1") (pinfunction "1_1") (pintype "passive"))
      (node (ref "CHANGE_BUTTON") (pin "3") (pinfunction "3_3") (pintype "passive"))
      (node (ref "CHANGE_BUTTON") (pin "4") (pinfunction "4_4") (pintype "passive"))
      (node (ref "R_CHANGE") (pin "1") (pinfunction "1_1") (pintype "passive"))
      (node (ref "U2") (pin "23") (pinfunction "IO15_23") (pintype "bidirectional"))
    )
    (net (code "19") (name "MISO") (class "Default")
      (node (ref "D12") (pin "2") (pinfunction "2_2") (pintype "passive"))
      (node (ref "J4") (pin "P7") (pinfunction "DAT0_P7") (pintype "bidirectional"))
      (node (ref "MISO") (pin "TP") (pinfunction "TP_TP") (pintype "input"))
      (node (ref "R8") (pin "1") (pinfunction "1_1") (pintype "passive"))
      (node (ref "U1") (pin "2") (pinfunction "DO(IO1)_2") (pintype "bidirectional"))
      (node (ref "U2") (pin "27") (pinfunction "IO2_27") (pintype "bidirectional"))
    )
    (net (code "20") (name "MOSI") (class "Default")
      (node (ref "D11") (pin "2") (pinfunction "2_2") (pintype "passive"))
      (node (ref "J1") (pin "14") (pinfunction "14_14") (pintype "bidirectional"))
      (node (ref "J4") (pin "P3") (pinfunction "CMD_P3") (pintype "bidirectional"))
      (node (ref "MOSI") (pin "TP") (pinfunction "TP_TP") (pintype "input"))
      (node (ref "R7") (pin "1") (pinfunction "1_1") (pintype "passive"))
      (node (ref "U1") (pin "5") (pinfunction "DI(IO0)_5") (pintype "bidirectional"))
      (node (ref "U2") (pin "7") (pinfunction "IO7_7") (pintype "bidirectional"))
    )
    (net (code "21") (name "Net-(CHG_LED-PadC)") (class "Default")
      (node (ref "CHG_LED") (pin "C") (pinfunction "C_C") (pintype "passive"))
      (node (ref "R1_BAT") (pin "1") (pinfunction "1_1") (pintype "passive"))
    )
    (net (code "22") (name "Net-(D2-CATHODE)") (class "Default")
      (node (ref "C1_BAT1") (pin "1") (pinfunction "1_1") (pintype "passive"))
      (node (ref "D2") (pin "1") (pinfunction "CATHODE_1") (pintype "bidirectional"))
      (node (ref "IC4") (pin "1") (pinfunction "VIN_1") (pintype "bidirectional"))
      (node (ref "IC4") (pin "3") (pinfunction "CE_3") (pintype "bidirectional"))
      (node (ref "Q1") (pin "2") (pinfunction "S_2") (pintype "bidirectional"))
    )
    (net (code "23") (name "Net-(D3-A)") (class "Default")
      (node (ref "C4") (pin "1") (pinfunction "1_1") (pintype "passive"))
      (node (ref "D3") (pin "2") (pinfunction "A_2") (pintype "bidirectional"))
      (node (ref "D4") (pin "1") (pinfunction "K_1") (pintype "bidirectional"))
    )
    (net (code "24") (name "Net-(D7-CATHODE)") (class "Default")
      (node (ref "D7") (pin "1") (pinfunction "CATHODE_1") (pintype "bidirectional"))
      (node (ref "R_CAPACITOR") (pin "1") (pinfunction "1_1") (pintype "passive"))
    )
    (net (code "25") (name "Net-(EPD_C1-Pad2)") (class "Default")
      (node (ref "EPD_C1") (pin "2") (pinfunction "2_2") (pintype "passive"))
      (node (ref "J1") (pin "4") (pinfunction "4_4") (pintype "bidirectional"))
    )
    (net (code "26") (name "Net-(EPD_C2-Pad2)") (class "Default")
      (node (ref "EPD_C2") (pin "2") (pinfunction "2_2") (pintype "passive"))
      (node (ref "J1") (pin "5") (pinfunction "5_5") (pintype "bidirectional"))
    )
    (net (code "27") (name "Net-(EPD_C6-Pad2)") (class "Default")
      (node (ref "EPD_C6") (pin "2") (pinfunction "2_2") (pintype "passive"))
      (node (ref "J1") (pin "18") (pinfunction "18_18") (pintype "bidirectional"))
    )
    (net (code "28") (name "Net-(EPD_C7\\-Pad2)") (class "Default")
      (node (ref "EPD_C7\\") (pin "2") (pinfunction "2_2") (pintype "passive"))
      (node (ref "J1") (pin "19") (pinfunction "19_19") (pintype "bidirectional"))
    )
    (net (code "29") (name "Net-(EPD_C8-Pad2)") (class "Default")
      (node (ref "EPD_C8") (pin "2") (pinfunction "2_2") (pintype "passive"))
      (node (ref "J1") (pin "20") (pinfunction "20_20") (pintype "bidirectional"))
    )
    (net (code "30") (name "Net-(EPD_C10-Pad2)") (class "Default")
      (node (ref "EPD_C10") (pin "2") (pinfunction "2_2") (pintype "passive"))
      (node (ref "J1") (pin "22") (pinfunction "22_22") (pintype "bidirectional"))
    )
    (net (code "31") (name "Net-(EPD_C12-Pad2)") (class "Default")
      (node (ref "EPD_C12") (pin "2") (pinfunction "2_2") (pintype "passive"))
      (node (ref "J1") (pin "24") (pinfunction "24_24") (pintype "bidirectional"))
    )
    (net (code "32") (name "Net-(IC1-CT)") (class "Default")
      (node (ref "C_DELAY") (pin "1") (pinfunction "1_1") (pintype "passive"))
      (node (ref "IC1") (pin "5") (pinfunction "CT_5") (pintype "bidirectional"))
    )
    (net (code "33") (name "Net-(J2-PadA5)") (class "Default")
      (node (ref "J2") (pin "A5") (pinfunction "A5_A5") (pintype "bidirectional"))
      (node (ref "R2-USB1") (pin "2") (pinfunction "2_2") (pintype "passive"))
    )
    (net (code "34") (name "Net-(J2-PadB5)") (class "Default")
      (node (ref "J2") (pin "B5") (pinfunction "B5_B5") (pintype "bidirectional"))
      (node (ref "R2-USB") (pin "1") (pinfunction "1_1") (pintype "passive"))
    )
    (net (code "35") (name "Net-(MCP73831-PROG)") (class "Default")
      (node (ref "MCP73831") (pin "5") (pinfunction "PROG_5") (pintype "input"))
      (node (ref "R2_BAT") (pin "2") (pinfunction "2_2") (pintype "passive"))
    )
    (net (code "36") (name "Net-(MCP73831-STAT)") (class "Default")
      (node (ref "MCP73831") (pin "1") (pinfunction "STAT_1") (pintype "output"))
      (node (ref "R1_BAT") (pin "2") (pinfunction "2_2") (pintype "passive"))
    )
    (net (code "37") (name "PREVGH") (class "Default")
      (node (ref "D5") (pin "1") (pinfunction "K_1") (pintype "bidirectional"))
      (node (ref "EPD_C9") (pin "2") (pinfunction "2_2") (pintype "passive"))
      (node (ref "J1") (pin "21") (pinfunction "21_21") (pintype "bidirectional"))
    )
    (net (code "38") (name "PREVGL") (class "Default")
      (node (ref "D4") (pin "2") (pinfunction "A_2") (pintype "bidirectional"))
      (node (ref "EPD_C11") (pin "2") (pinfunction "2_2") (pintype "passive"))
      (node (ref "J1") (pin "23") (pinfunction "23_23") (pintype "bidirectional"))
    )
    (net (code "39") (name "RESE") (class "Default")
      (node (ref "J1") (pin "3") (pinfunction "3_3") (pintype "bidirectional"))
      (node (ref "Q3") (pin "2") (pinfunction "S_2") (pintype "bidirectional"))
      (node (ref "R3") (pin "2") (pinfunction "2_2") (pintype "passive"))
    )
    (net (code "40") (name "RESE'") (class "Default")
      (node (ref "R2") (pin "2") (pinfunction "2_2") (pintype "passive"))
      (node (ref "R3") (pin "1") (pinfunction "1_1") (pintype "passive"))
      (node (ref "SJ1") (pin "2") (pinfunction "2_2") (pintype "passive"))
    )
    (net (code "41") (name "RESET") (class "Default")
      (node (ref "C5") (pin "1") (pinfunction "1_1") (pintype "passive"))
      (node (ref "IC1") (pin "1") (pinfunction "VOUT_1") (pintype "bidirectional"))
      (node (ref "RESET_BUTTON") (pin "3") (pinfunction "3_3") (pintype "passive"))
      (node (ref "RESET_BUTTON") (pin "4") (pinfunction "4_4") (pintype "passive"))
      (node (ref "R_RESET") (pin "1") (pinfunction "1_1") (pintype "passive"))
      (node (ref "U2") (pin "3") (pinfunction "EN_3") (pintype "input"))
    )
    (net (code "42") (name "RTC_RST") (class "Default")
      (node (ref "U2") (pin "16") (pinfunction "IO18_16") (pintype "bidirectional"))
      (node (ref "U3") (pin "4") (pinfunction "~{RST}_4") (pintype "input"))
    )
    (net (code "43") (name "RX") (class "Default")
      (node (ref "RX") (pin "TP") (pinfunction "TP_TP") (pintype "input"))
      (node (ref "U2") (pin "24") (pinfunction "RXD0/GPIO17_24") (pintype "bidirectional"))
    )
    (net (code "44") (name "SCK") (class "Default")
      (node (ref "D10") (pin "2") (pinfunction "2_2") (pintype "passive"))
      (node (ref "J1") (pin "13") (pinfunction "13_13") (pintype "bidirectional"))
      (node (ref "J4") (pin "P5") (pinfunction "CLK_P5") (pintype "bidirectional"))
      (node (ref "R6") (pin "1") (pinfunction "1_1") (pintype "passive"))
      (node (ref "SCK") (pin "TP") (pinfunction "TP_TP") (pintype "input"))
      (node (ref "U1") (pin "6") (pinfunction "CLK_6") (pintype "input"))
      (node (ref "U2") (pin "6") (pinfunction "IO6_6") (pintype "bidirectional"))
    )
    (net (code "45") (name "SCL") (class "Default")
      (node (ref "J3") (pin "4") (pinfunction "4_4") (pintype "passive"))
      (node (ref "R2-PINH") (pin "1") (pinfunction "1_1") (pintype "passive"))
      (node (ref "SENSOR2") (pin "4") (pinfunction "SCK_4") (pintype "input"))
      (node (ref "U2") (pin "20") (pinfunction "IO22_20") (pintype "bidirectional"))
      (node (ref "U3") (pin "16") (pinfunction "SCL_16") (pintype "input"))
      (node (ref "U4") (pin "7") (pinfunction "SCL_7") (pintype "input"))
    )
    (net (code "46") (name "SDA") (class "Default")
      (node (ref "J3") (pin "3") (pinfunction "3_3") (pintype "passive"))
      (node (ref "R1_PINH") (pin "1") (pinfunction "1_1") (pintype "passive"))
      (node (ref "SENSOR2") (pin "3") (pinfunction "SDI_3") (pintype "bidirectional"))
      (node (ref "U2") (pin "19") (pinfunction "IO21_19") (pintype "bidirectional"))
      (node (ref "U3") (pin "15") (pinfunction "SDA_15") (pintype "bidirectional"))
      (node (ref "U4") (pin "8") (pinfunction "SDA_8") (pintype "bidirectional"))
    )
    (net (code "47") (name "SRC") (class "Default")
      (node (ref "C4") (pin "2") (pinfunction "2_2") (pintype "passive"))
      (node (ref "D5") (pin "2") (pinfunction "A_2") (pintype "bidirectional"))
      (node (ref "L1") (pin "1") (pinfunction "1_1") (pintype "passive"))
      (node (ref "Q3") (pin "3") (pinfunction "D_3") (pintype "bidirectional"))
    )
    (net (code "48") (name "SS_SD") (class "Default")
      (node (ref "D8") (pin "2") (pinfunction "2_2") (pintype "passive"))
      (node (ref "J4") (pin "P2") (pinfunction "CD/DAT3_P2") (pintype "bidirectional"))
      (node (ref "R10") (pin "1") (pinfunction "1_1") (pintype "passive"))
      (node (ref "U2") (pin "4") (pinfunction "IO4_4") (pintype "bidirectional"))
    )
    (net (code "49") (name "TX") (class "Default")
      (node (ref "TX") (pin "TP") (pinfunction "TP_TP") (pintype "input"))
      (node (ref "U2") (pin "25") (pinfunction "TXD0/GPIO16_25") (pintype "bidirectional"))
    )
    (net (code "50") (name "USB_D+") (class "Default")
      (node (ref "D1") (pin "1") (pinfunction "I/O1_1_1") (pintype "bidirectional"))
      (node (ref "U2") (pin "14") (pinfunction "IO13_14") (pintype "bidirectional"))
    )
    (net (code "51") (name "USB_D-") (class "Default")
      (node (ref "D1") (pin "3") (pinfunction "I/O2_1_3") (pintype "bidirectional"))
      (node (ref "U2") (pin "13") (pinfunction "IO12_13") (pintype "bidirectional"))
    )
    (net (code "52") (name "VBAT") (class "Default")
      (node (ref "C2_BAT") (pin "1") (pinfunction "1_1") (pintype "passive"))
      (node (ref "MCP73831") (pin "3") (pinfunction "VBAT_3") (pintype "power_in"))
      (node (ref "Q1") (pin "3") (pinfunction "D_3") (pintype "bidirectional"))
      (node (ref "U4") (pin "2") (pinfunction "CELL_2") (pintype "power_in"))
      (node (ref "U4") (pin "3") (pinfunction "VDD_3") (pintype "power_in"))
      (node (ref "VBAT") (pin "TP") (pinfunction "TP_TP") (pintype "input"))
    )
    (net (code "53") (name "VBUS") (class "Default")
      (node (ref "C1_BAT") (pin "1") (pinfunction "1_1") (pintype "passive"))
      (node (ref "C4_USB") (pin "1") (pinfunction "1_1") (pintype "passive"))
      (node (ref "C5_USB") (pin "1") (pinfunction "1_1") (pintype "passive"))
      (node (ref "CHG_LED") (pin "A") (pinfunction "A_A") (pintype "passive"))
      (node (ref "D1") (pin "5") (pinfunction "VBUS_5") (pintype "bidirectional"))
      (node (ref "D2") (pin "2") (pinfunction "ANODE_2") (pintype "bidirectional"))
      (node (ref "MCP73831") (pin "4") (pinfunction "VIN_4") (pintype "power_in"))
      (node (ref "PFMF.050.1") (pin "2") (pinfunction "2_2") (pintype "passive"))
      (node (ref "Q1") (pin "1") (pinfunction "G_1") (pintype "bidirectional"))
      (node (ref "R1_PWRUSB") (pin "2") (pinfunction "2_2") (pintype "passive"))
      (node (ref "VBUS") (pin "TP") (pinfunction "TP_TP") (pintype "input"))
    )
    (net (code "54") (name "VRTC") (class "Default")
      (node (ref "C10_SUPERCAP") (pin "2") (pinfunction "2_2") (pintype "passive"))
      (node (ref "C8") (pin "1") (pinfunction "1_1") (pintype "passive"))
      (node (ref "R_CAPACITOR") (pin "2") (pinfunction "2_2") (pintype "passive"))
      (node (ref "U3") (pin "14") (pinfunction "VBAT_14") (pintype "power_in"))
    )
    (net (code "55") (name "VUSB") (class "Default")
      (node (ref "J2") (pin "A4") (pinfunction "A4_A4") (pintype "bidirectional"))
      (node (ref "J2") (pin "A9") (pinfunction "A9_A9") (pintype "bidirectional"))
      (node (ref "J2") (pin "B4") (pinfunction "B4_B4") (pintype "bidirectional"))
      (node (ref "J2") (pin "B9") (pinfunction "B9_B9") (pintype "bidirectional"))
      (node (ref "PFMF.050.1") (pin "1") (pinfunction "1_1") (pintype "passive"))
    )
    (net (code "56") (name "unconnected-(IC1-NC-Pad4)") (class "Default")
      (node (ref "IC1") (pin "4") (pinfunction "NC_4") (pintype "no_connect"))
    )
    (net (code "57") (name "unconnected-(IC4-NC-Pad4)") (class "Default")
      (node (ref "IC4") (pin "4") (pinfunction "NC_4") (pintype "no_connect"))
    )
    (net (code "58") (name "unconnected-(J1-Pad1)") (class "Default")
      (node (ref "J1") (pin "1") (pinfunction "1_1") (pintype "bidirectional"))
    )
    (net (code "59") (name "unconnected-(J1-Pad6)") (class "Default")
      (node (ref "J1") (pin "6") (pinfunction "6_6") (pintype "bidirectional"))
    )
    (net (code "60") (name "unconnected-(J1-Pad7)") (class "Default")
      (node (ref "J1") (pin "7") (pinfunction "7_7") (pintype "bidirectional"))
    )
    (net (code "61") (name "unconnected-(J2-PadA8)") (class "Default")
      (node (ref "J2") (pin "A8") (pinfunction "A8_A8") (pintype "bidirectional"))
    )
    (net (code "62") (name "unconnected-(J2-PadB8)") (class "Default")
      (node (ref "J2") (pin "B8") (pinfunction "B8_B8") (pintype "bidirectional"))
    )
    (net (code "63") (name "unconnected-(J4-DAT1-PadP8)") (class "Default")
      (node (ref "J4") (pin "P8") (pinfunction "DAT1_P8") (pintype "bidirectional"))
    )
    (net (code "64") (name "unconnected-(J4-DAT2-PadP1)") (class "Default")
      (node (ref "J4") (pin "P1") (pinfunction "DAT2_P1") (pintype "bidirectional"))
    )
    (net (code "65") (name "unconnected-(J4-DETECTION_1-PadS1)") (class "Default")
      (node (ref "J4") (pin "S1") (pinfunction "DETECTION_1_S1") (pintype "bidirectional"))
    )
    (net (code "66") (name "unconnected-(J4-DETECTION_2-PadS2)") (class "Default")
      (node (ref "J4") (pin "S2") (pinfunction "DETECTION_2_S2") (pintype "bidirectional"))
    )
    (net (code "67") (name "unconnected-(U2-NC-Pad22)") (class "Default")
      (node (ref "U2") (pin "22") (pinfunction "NC_22") (pintype "no_connect"))
    )
    (net (code "68") (name "unconnected-(U4-~{ALERT}-Pad5)") (class "Default")
      (node (ref "U4") (pin "5") (pinfunction "~{ALERT}_5") (pintype "output"))
    )
  )
)
